# Contrast_V1_0.net
KiCad netlist of a schematic drawn in EAGLE
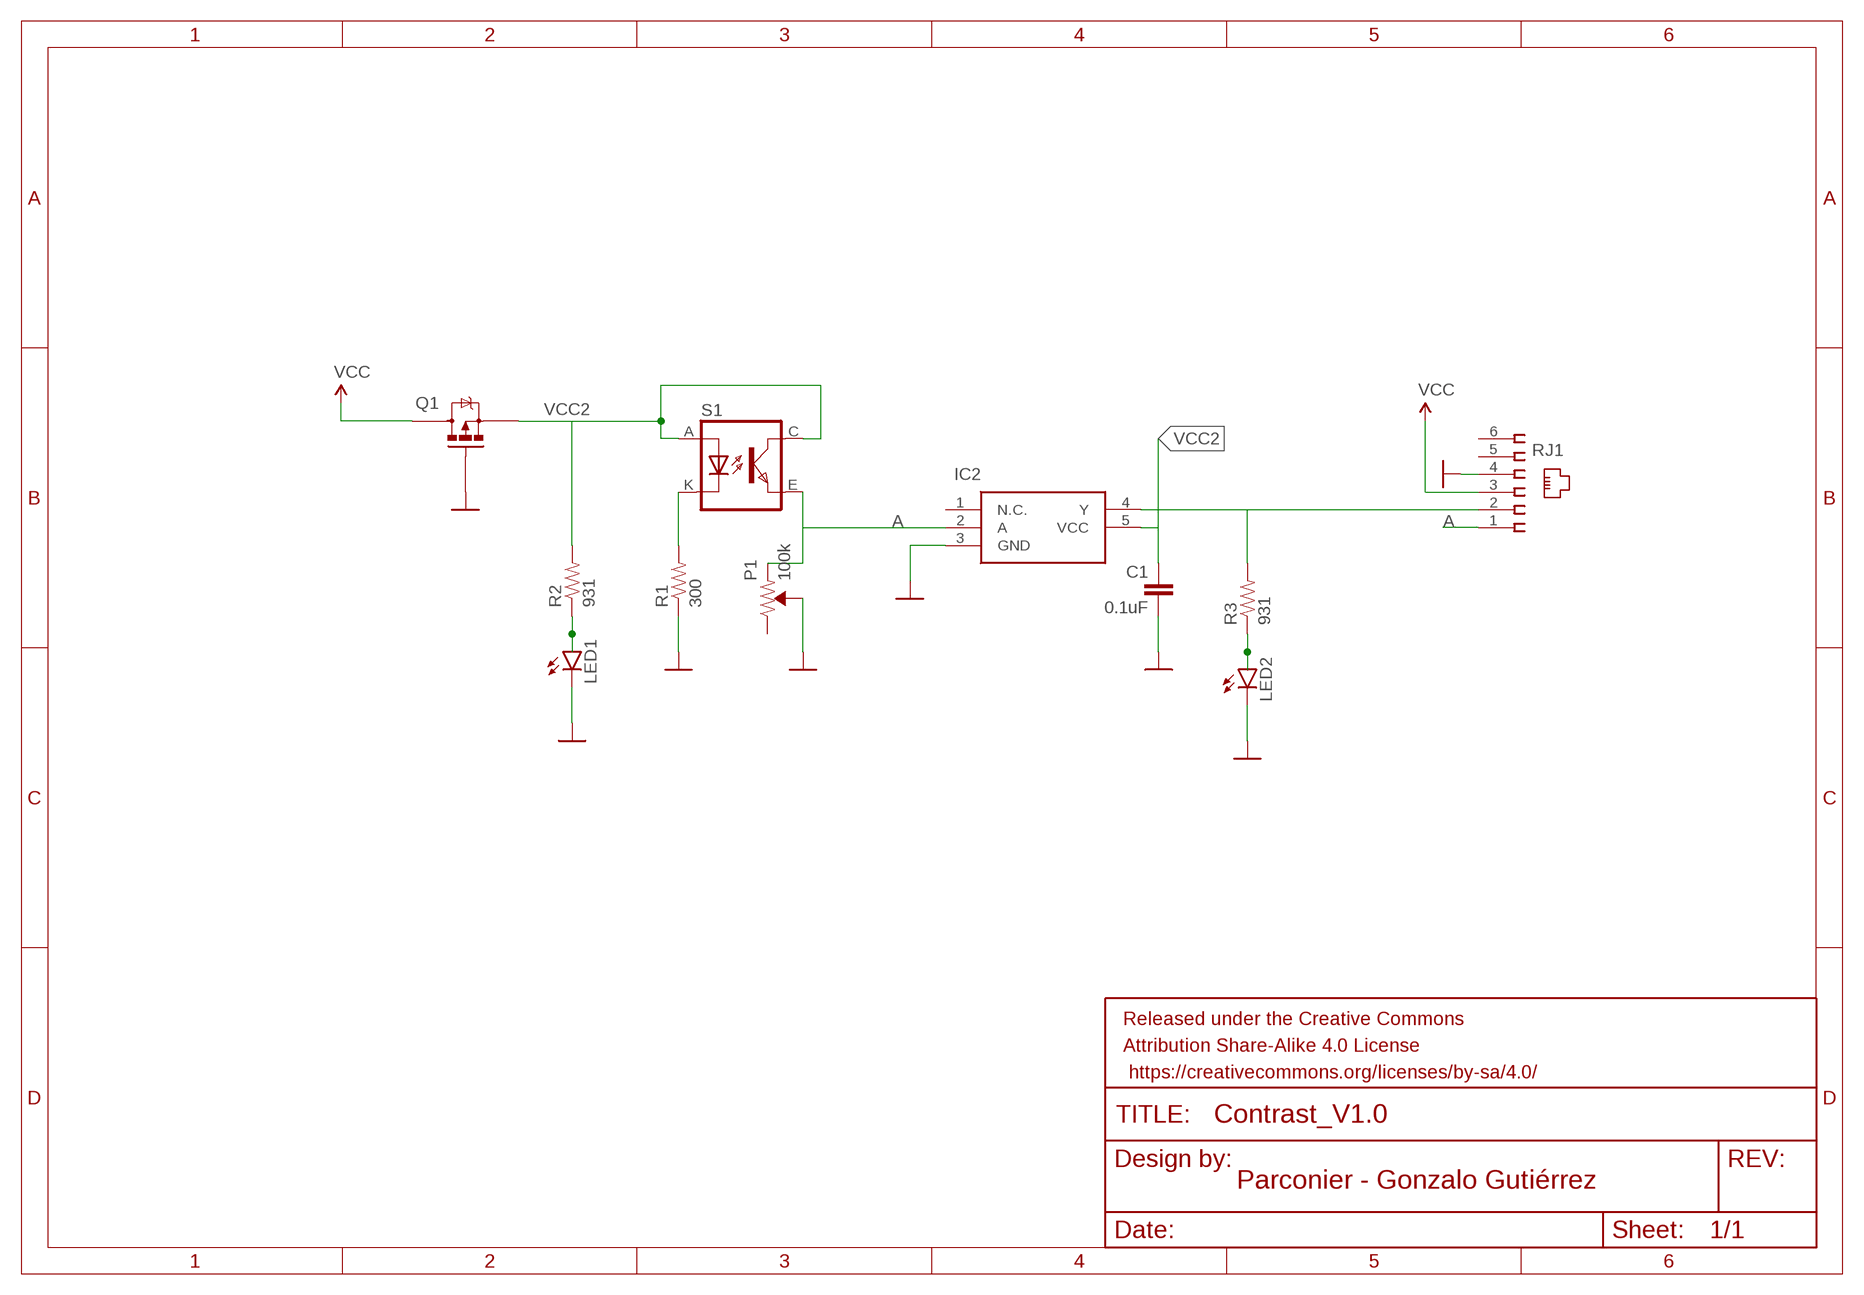
[diagram p0: schematic, sheet 1]

(export (version "E")
  (design (tool "Eeschema 10.0.6"))
  (components
    (comp (ref "C1")
      (value "0.1uF")
      (footprint "eagle-import:0402")
      (fields (field (name "MPN") "CC0402KRX5R9BB104"))
      (libsource (lib "eagle-import") (part "CAP_0402"))
    )
    (comp (ref "IC2")
      (value "74LVC1G14GW-Q100,1")
      (footprint "eagle-import:SOT65P212X110-5N")
      (fields (field (name "RS_PART_NUMBER") "1526474") (field (name "MPN") "74AHC1G14GW-Q100,1"))
      (libsource (lib "eagle-import") (part "74LVC1G14GW-Q100,1"))
    )
    (comp (ref "LED1")
      (value "LED0603")
      (footprint "eagle-import:LED-0603")
      (fields (field (name "MPN") "LTST-C193KRKT-5A "))
      (libsource (lib "eagle-import") (part "LED0603"))
    )
    (comp (ref "LED2")
      (value "LED0603")
      (footprint "eagle-import:LED-0603")
      (fields (field (name "MPN") "LB Q39E-L2OO-35-1"))
      (libsource (lib "eagle-import") (part "LED0603"))
    )
    (comp (ref "P1")
      (value "100k")
      (footprint "eagle-import:3309W-1-104")
      (fields (field (name "MPN") "3309W-1-104"))
      (libsource (lib "eagle-import") (part "TRIMPOT"))
    )
    (comp (ref "Q1")
      (value "RU1C002ZPTCL")
      (footprint "eagle-import:SOTFL65P210X105-3N")
      (libsource (lib "eagle-import") (part "RU1C002ZPTCL"))
    )
    (comp (ref "R1")
      (value "300")
      (footprint "eagle-import:RESC1005X35")
      (fields (field (name "MPN") "RC0402JR-07300RL"))
      (libsource (lib "eagle-import") (part "RES_0402"))
    )
    (comp (ref "R2")
      (value "931")
      (footprint "eagle-import:RESC1005X35")
      (fields (field (name "MPN") "RC0402FR-07931RL"))
      (libsource (lib "eagle-import") (part "RES_0402"))
    )
    (comp (ref "R3")
      (value "931")
      (footprint "eagle-import:RESC1005X35")
      (fields (field (name "MPN") "RC0402FR-07931RL"))
      (libsource (lib "eagle-import") (part "RES_0402"))
    )
    (comp (ref "RJ1")
      (value "615006138421")
      (footprint "eagle-import:615006138421")
      (fields (field (name "RS_PART_NUMBER") "7350282") (field (name "MPN") "54601-906WPLF"))
      (libsource (lib "eagle-import") (part "615006138421"))
    )
    (comp (ref "S1")
      (value "TCRT5000")
      (footprint "eagle-import:TCRT5000")
      (libsource (lib "eagle-import") (part "TCRT5000"))
    )
  )
  (nets
    (net (code "1") (name "/A") (class "Default")
      (node (ref "IC2") (pin "2") (pinfunction "A_2") (pintype "bidirectional"))
      (node (ref "P1") (pin "1") (pinfunction "CCW_1") (pintype "passive"))
      (node (ref "RJ1") (pin "1") (pinfunction "1_1") (pintype "input"))
      (node (ref "S1") (pin "E") (pinfunction "EMITTER_E") (pintype "passive"))
    )
    (net (code "2") (name "GND") (class "Default")
      (node (ref "C1") (pin "2") (pinfunction "2_2") (pintype "passive"))
      (node (ref "IC2") (pin "3") (pinfunction "GND_3") (pintype "bidirectional"))
      (node (ref "LED1") (pin "C") (pinfunction "C_C") (pintype "passive"))
      (node (ref "LED2") (pin "C") (pinfunction "C_C") (pintype "passive"))
      (node (ref "P1") (pin "2") (pinfunction "WIPER_2") (pintype "passive"))
      (node (ref "Q1") (pin "1") (pinfunction "G_1") (pintype "bidirectional"))
      (node (ref "R1") (pin "1") (pinfunction "1_1") (pintype "passive"))
      (node (ref "RJ1") (pin "4") (pinfunction "4_4") (pintype "input"))
    )
    (net (code "3") (name "Net-(IC2-Y)") (class "Default")
      (node (ref "IC2") (pin "4") (pinfunction "Y_4") (pintype "bidirectional"))
      (node (ref "R3") (pin "2") (pinfunction "2_2") (pintype "passive"))
      (node (ref "RJ1") (pin "2") (pinfunction "2_2") (pintype "input"))
    )
    (net (code "4") (name "Net-(LED1-PadA)") (class "Default")
      (node (ref "LED1") (pin "A") (pinfunction "A_A") (pintype "passive"))
      (node (ref "R2") (pin "1") (pinfunction "1_1") (pintype "passive"))
    )
    (net (code "5") (name "Net-(LED2-PadA)") (class "Default")
      (node (ref "LED2") (pin "A") (pinfunction "A_A") (pintype "passive"))
      (node (ref "R3") (pin "1") (pinfunction "1_1") (pintype "passive"))
    )
    (net (code "6") (name "Net-(S1-CATHODE)") (class "Default")
      (node (ref "R1") (pin "2") (pinfunction "2_2") (pintype "passive"))
      (node (ref "S1") (pin "K") (pinfunction "CATHODE_K") (pintype "passive"))
    )
    (net (code "7") (name "VCC") (class "Default")
      (node (ref "Q1") (pin "3") (pinfunction "D_3") (pintype "bidirectional"))
      (node (ref "RJ1") (pin "3") (pinfunction "3_3") (pintype "input"))
    )
    (net (code "8") (name "VCC2") (class "Default")
      (node (ref "C1") (pin "1") (pinfunction "1_1") (pintype "passive"))
      (node (ref "IC2") (pin "5") (pinfunction "VCC_5") (pintype "bidirectional"))
      (node (ref "Q1") (pin "2") (pinfunction "S_2") (pintype "bidirectional"))
      (node (ref "R2") (pin "2") (pinfunction "2_2") (pintype "passive"))
      (node (ref "S1") (pin "A") (pinfunction "ANODE_A") (pintype "passive"))
      (node (ref "S1") (pin "C") (pinfunction "COLLECTOR_C") (pintype "passive"))
    )
    (net (code "9") (name "unconnected-(IC2-N.C.-Pad1)") (class "Default")
      (node (ref "IC2") (pin "1") (pinfunction "N.C._1") (pintype "no_connect"))
    )
    (net (code "10") (name "unconnected-(P1-CW-Pad3)") (class "Default")
      (node (ref "P1") (pin "3") (pinfunction "CW_3") (pintype "passive"))
    )
    (net (code "11") (name "unconnected-(RJ1-Pad5)") (class "Default")
      (node (ref "RJ1") (pin "5") (pinfunction "5_5") (pintype "input"))
    )
    (net (code "12") (name "unconnected-(RJ1-Pad6)") (class "Default")
      (node (ref "RJ1") (pin "6") (pinfunction "6_6") (pintype "input"))
    )
  )
)
